# neodk_v1.net
KiCad netlist of a schematic drawn in EAGLE
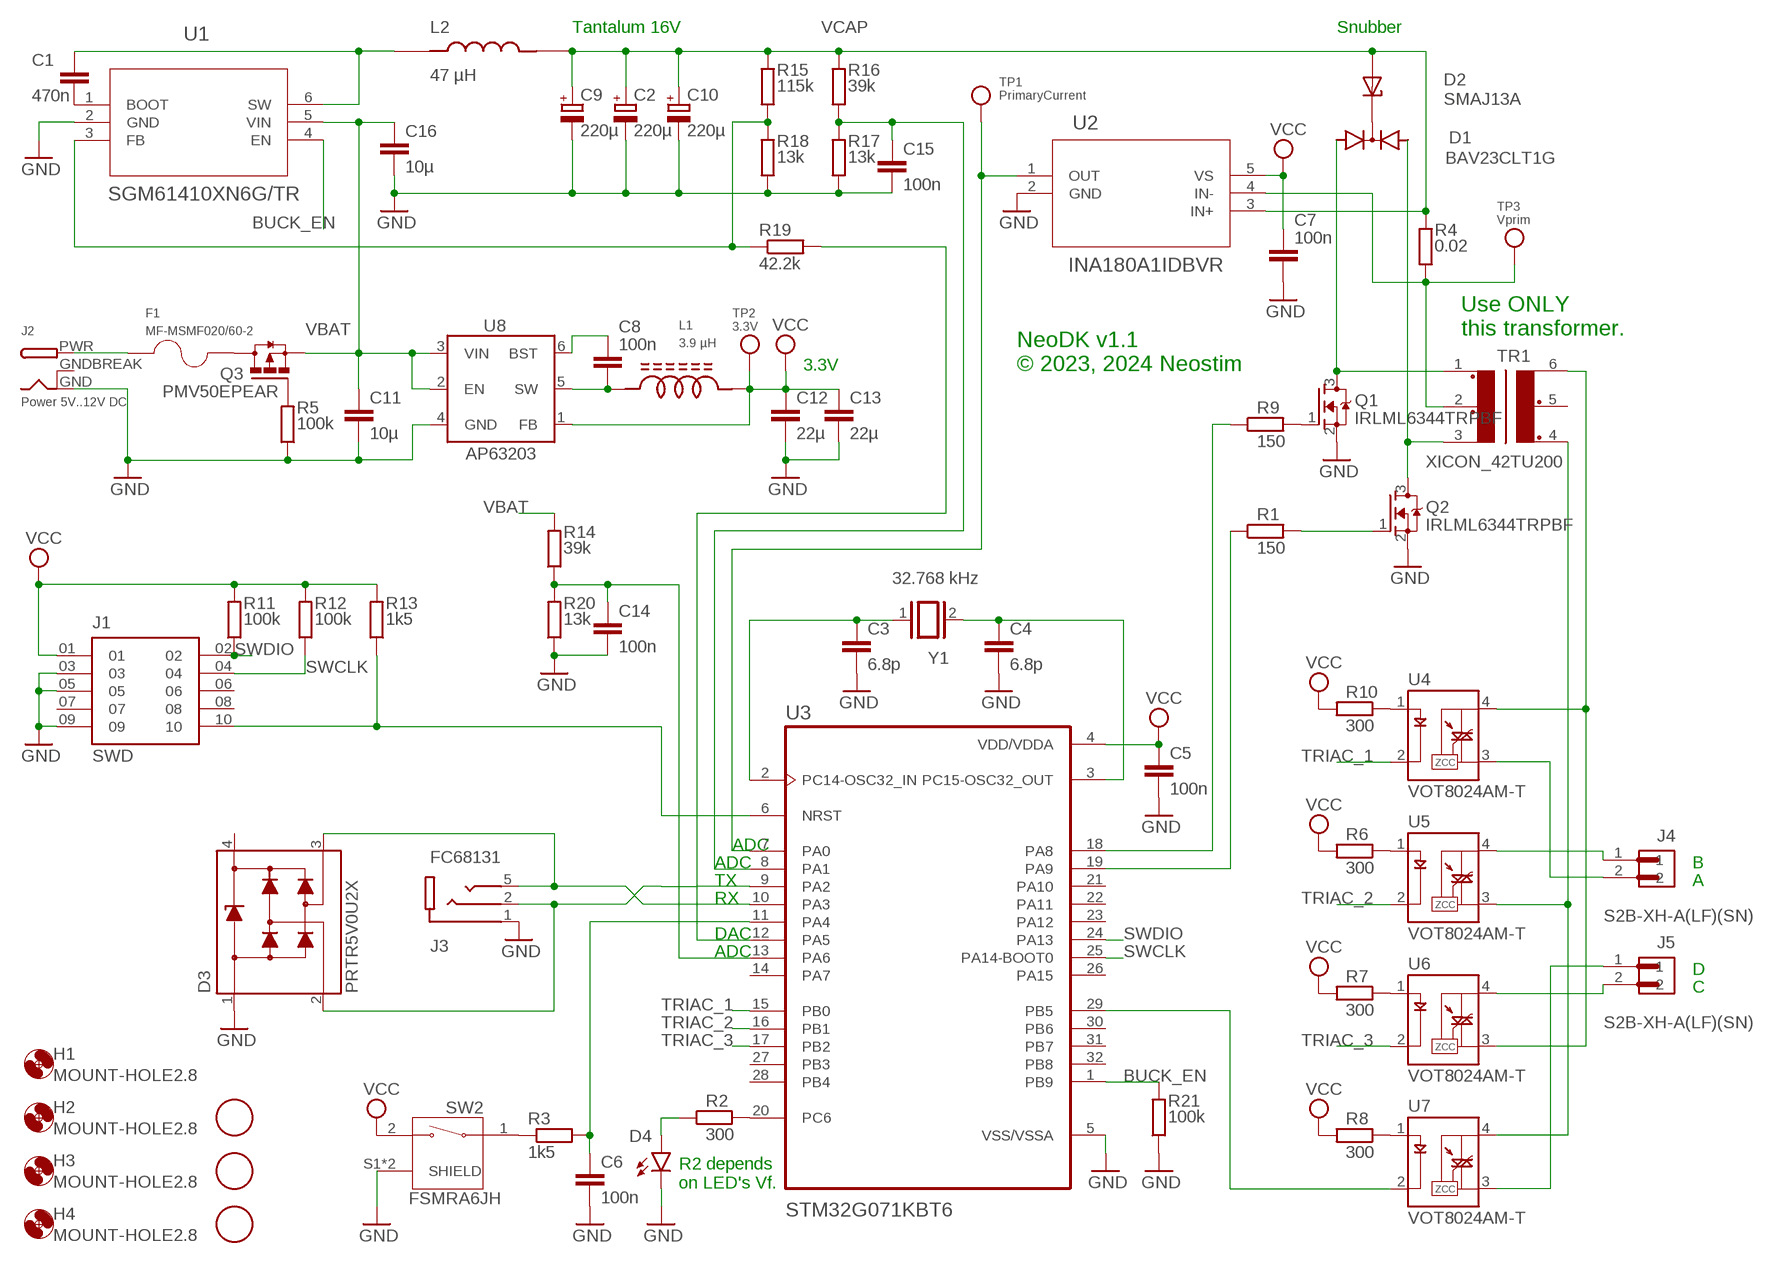
[diagram p0: schematic, sheet 1]

(export (version "E")
  (design (tool "Eeschema 10.0.6"))
  (components
    (comp (ref "C1")
      (value "470n")
      (footprint "eagle-import:C0603")
      (libsource (lib "eagle-import") (part "C-EUC0603"))
    )
    (comp (ref "C2")
      (value "220µ")
      (footprint "eagle-import:SMC_D")
      (fields (field (name "MP") "TPSE227M016R0150"))
      (libsource (lib "eagle-import") (part "CPOL-EUSMCD"))
    )
    (comp (ref "C3")
      (value "6.8p")
      (footprint "eagle-import:C0603")
      (libsource (lib "eagle-import") (part "C-EUC0603"))
    )
    (comp (ref "C4")
      (value "6.8p")
      (footprint "eagle-import:C0603")
      (libsource (lib "eagle-import") (part "C-EUC0603"))
    )
    (comp (ref "C5")
      (value "100n")
      (footprint "eagle-import:C0603")
      (libsource (lib "eagle-import") (part "C-EUC0603"))
    )
    (comp (ref "C6")
      (value "100n")
      (footprint "eagle-import:C0603")
      (libsource (lib "eagle-import") (part "C-EUC0603"))
    )
    (comp (ref "C7")
      (value "100n")
      (footprint "eagle-import:C0603")
      (libsource (lib "eagle-import") (part "C-EUC0603"))
    )
    (comp (ref "C8")
      (value "100n")
      (footprint "eagle-import:C0603")
      (libsource (lib "eagle-import") (part "C-EUC0603"))
    )
    (comp (ref "C9")
      (value "220µ")
      (footprint "eagle-import:SMC_D")
      (fields (field (name "MP") "TPSE227M016R0150"))
      (libsource (lib "eagle-import") (part "CPOL-EUSMCD"))
    )
    (comp (ref "C10")
      (value "220µ")
      (footprint "eagle-import:SMC_D")
      (fields (field (name "MP") "TPSE227M016R0150"))
      (libsource (lib "eagle-import") (part "CPOL-EUSMCD"))
    )
    (comp (ref "C11")
      (value "10µ")
      (footprint "eagle-import:C0603")
      (libsource (lib "eagle-import") (part "C-EUC0603"))
    )
    (comp (ref "C12")
      (value "22µ")
      (footprint "eagle-import:C0603")
      (libsource (lib "eagle-import") (part "C-EUC0603"))
    )
    (comp (ref "C13")
      (value "22µ")
      (footprint "eagle-import:C0603")
      (libsource (lib "eagle-import") (part "C-EUC0603"))
    )
    (comp (ref "C14")
      (value "100n")
      (footprint "eagle-import:C0603")
      (libsource (lib "eagle-import") (part "C-EUC0603"))
    )
    (comp (ref "C15")
      (value "100n")
      (footprint "eagle-import:C0603")
      (libsource (lib "eagle-import") (part "C-EUC0603"))
    )
    (comp (ref "C16")
      (value "10µ")
      (footprint "eagle-import:C0603")
      (libsource (lib "eagle-import") (part "C-EUC0603"))
    )
    (comp (ref "D1")
      (value "BAV23CLT1G")
      (footprint "eagle-import:SOT23")
      (libsource (lib "eagle-import") (part "DIODE-2AC|CASOT23"))
    )
    (comp (ref "D2")
      (value "SMAJ13A")
      (footprint "eagle-import:DIOM4325X250N")
      (fields (field (name "MF") "STMicroelectronics") (field (name "MP") "SMAJ13A-TR"))
      (libsource (lib "eagle-import") (part "SMAJ13A"))
    )
    (comp (ref "D3")
      (value "PRTR5V0U2X")
      (footprint "eagle-import:SOT190P230X110-4N")
      (fields (field (name "MF") "Nexperia USA"))
      (libsource (lib "eagle-import") (part "PRTR5V0U2X"))
    )
    (comp (ref "D4")
      (value "LEDCHIP-LED0805")
      (footprint "eagle-import:CHIP-LED0805")
      (libsource (lib "eagle-import") (part "LEDCHIP-LED0805"))
    )
    (comp (ref "F1")
      (value "MF-MSMF020/60-2")
      (footprint "eagle-import:FUSER_MF-MSMF020_60-2")
      (fields (field (name "MF") "Bourns"))
      (libsource (lib "eagle-import") (part "MF-MSMF020/60-2"))
    )
    (comp (ref "FID1")
      (value "FIDUCIAL")
      (footprint "eagle-import:FIDUCIAL_1MM")
      (libsource (lib "eagle-import") (part "FIDUCIAL"))
    )
    (comp (ref "FID2")
      (value "FIDUCIAL")
      (footprint "eagle-import:FIDUCIAL_1MM")
      (libsource (lib "eagle-import") (part "FIDUCIAL"))
    )
    (comp (ref "FID3")
      (value "FIDUCIAL")
      (footprint "eagle-import:FIDUCIAL_1MM")
      (libsource (lib "eagle-import") (part "FIDUCIAL"))
    )
    (comp (ref "H1")
      (value "MOUNT-HOLE2.8")
      (footprint "eagle-import:2,8")
      (libsource (lib "eagle-import") (part "MOUNT-HOLE2.8"))
    )
    (comp (ref "H2")
      (value "MOUNT-HOLE2.8")
      (footprint "eagle-import:2,8")
      (libsource (lib "eagle-import") (part "MOUNT-HOLE2.8"))
    )
    (comp (ref "H3")
      (value "MOUNT-HOLE2.8")
      (footprint "eagle-import:2,8")
      (libsource (lib "eagle-import") (part "MOUNT-HOLE2.8"))
    )
    (comp (ref "H4")
      (value "MOUNT-HOLE2.8")
      (footprint "eagle-import:2,8")
      (libsource (lib "eagle-import") (part "MOUNT-HOLE2.8"))
    )
    (comp (ref "J1")
      (value "SWD")
      (footprint "eagle-import:SAMTEC_FTSH-105-XX-X-DV")
      (fields (field (name "MF") "Samtec") (field (name "MP") "FTSH-105-01-L-DV"))
      (libsource (lib "eagle-import") (part "FTSH-105-XX-X-DV"))
    )
    (comp (ref "J2")
      (value "Power 5V..12V DC")
      (footprint "eagle-import:DCJACK_2MM_PTH")
      (libsource (lib "eagle-import") (part "DCBARRELPTH"))
    )
    (comp (ref "J3")
      (value "FC68131")
      (footprint "eagle-import:CLIFF_FC68131")
      (fields (field (name "MF") "Cliff"))
      (libsource (lib "eagle-import") (part "FC68131"))
    )
    (comp (ref "J4")
      (value "S2B-XH-A(LF)(SN)")
      (footprint "eagle-import:JST_S2B-XH-A(LF)(SN)")
      (fields (field (name "MF") "JST Sales"))
      (libsource (lib "eagle-import") (part "S2B-XH-A(LF)(SN)"))
    )
    (comp (ref "J5")
      (value "S2B-XH-A(LF)(SN)")
      (footprint "eagle-import:JST_S2B-XH-A(LF)(SN)")
      (fields (field (name "MF") "JST Sales"))
      (libsource (lib "eagle-import") (part "S2B-XH-A(LF)(SN)"))
    )
    (comp (ref "L1")
      (value "3.9 µH")
      (footprint "eagle-import:IND_SRR4818A-3R9Y")
      (fields (field (name "MF") "Bourns Inc.") (field (name "MP") "SRR4818A-3R9Y"))
      (libsource (lib "eagle-import") (part "SRR4818A-3R9Y"))
    )
    (comp (ref "L2")
      (value "47 µH")
      (footprint "eagle-import:IND_CLF7045NIT-470M-D")
      (fields (field (name "MF") "TDK") (field (name "MP") "CLF7045NIT-470M-D"))
      (libsource (lib "eagle-import") (part "CLF7045NIT-470M-D"))
    )
    (comp (ref "Q1")
      (value "IRLML6344TRPBF")
      (footprint "eagle-import:SOT23")
      (libsource (lib "eagle-import") (part "MOSFET-NREFLOW"))
    )
    (comp (ref "Q2")
      (value "IRLML6344TRPBF")
      (footprint "eagle-import:SOT23")
      (libsource (lib "eagle-import") (part "MOSFET-NREFLOW"))
    )
    (comp (ref "Q3")
      (value "PMV50EPEAR")
      (footprint "eagle-import:SOT23")
      (libsource (lib "eagle-import") (part "PMV50EPEAR"))
    )
    (comp (ref "R1")
      (value "150")
      (footprint "eagle-import:R0603")
      (libsource (lib "eagle-import") (part "R-EU_R0603"))
    )
    (comp (ref "R2")
      (value "300")
      (footprint "eagle-import:R0603")
      (libsource (lib "eagle-import") (part "R-EU_R0603"))
    )
    (comp (ref "R3")
      (value "1k5")
      (footprint "eagle-import:R0603")
      (libsource (lib "eagle-import") (part "R-EU_R0603"))
    )
    (comp (ref "R4")
      (value "0.02")
      (footprint "eagle-import:R1206")
      (libsource (lib "eagle-import") (part "R-EU_R1206"))
    )
    (comp (ref "R5")
      (value "100k")
      (footprint "eagle-import:R0603")
      (libsource (lib "eagle-import") (part "R-EU_R0603"))
    )
    (comp (ref "R6")
      (value "300")
      (footprint "eagle-import:R0603")
      (libsource (lib "eagle-import") (part "R-EU_R0603"))
    )
    (comp (ref "R7")
      (value "300")
      (footprint "eagle-import:R0603")
      (libsource (lib "eagle-import") (part "R-EU_R0603"))
    )
    (comp (ref "R8")
      (value "300")
      (footprint "eagle-import:R0603")
      (libsource (lib "eagle-import") (part "R-EU_R0603"))
    )
    (comp (ref "R9")
      (value "150")
      (footprint "eagle-import:R0603")
      (libsource (lib "eagle-import") (part "R-EU_R0603"))
    )
    (comp (ref "R10")
      (value "300")
      (footprint "eagle-import:R0603")
      (libsource (lib "eagle-import") (part "R-EU_R0603"))
    )
    (comp (ref "R11")
      (value "100k")
      (footprint "eagle-import:R0603")
      (libsource (lib "eagle-import") (part "R-EU_R0603"))
    )
    (comp (ref "R12")
      (value "100k")
      (footprint "eagle-import:R0603")
      (libsource (lib "eagle-import") (part "R-EU_R0603"))
    )
    (comp (ref "R13")
      (value "1k5")
      (footprint "eagle-import:R0603")
      (libsource (lib "eagle-import") (part "R-EU_R0603"))
    )
    (comp (ref "R14")
      (value "39k")
      (footprint "eagle-import:R0603")
      (libsource (lib "eagle-import") (part "R-EU_R0603"))
    )
    (comp (ref "R15")
      (value "115k")
      (footprint "eagle-import:R0603")
      (libsource (lib "eagle-import") (part "R-EU_R0603"))
    )
    (comp (ref "R16")
      (value "39k")
      (footprint "eagle-import:R0603")
      (libsource (lib "eagle-import") (part "R-EU_R0603"))
    )
    (comp (ref "R17")
      (value "13k")
      (footprint "eagle-import:R0603")
      (libsource (lib "eagle-import") (part "R-EU_R0603"))
    )
    (comp (ref "R18")
      (value "13k")
      (footprint "eagle-import:R0603")
      (libsource (lib "eagle-import") (part "R-EU_R0603"))
    )
    (comp (ref "R19")
      (value "42.2k")
      (footprint "eagle-import:R0603")
      (libsource (lib "eagle-import") (part "R-EU_R0603"))
    )
    (comp (ref "R20")
      (value "13k")
      (footprint "eagle-import:R0603")
      (libsource (lib "eagle-import") (part "R-EU_R0603"))
    )
    (comp (ref "R21")
      (value "100k")
      (footprint "eagle-import:R0603")
      (libsource (lib "eagle-import") (part "R-EU_R0603"))
    )
    (comp (ref "SW2")
      (value "FSMRA6JH")
      (footprint "eagle-import:TE_FSMRA6JH")
      (fields (field (name "MF") "TE Connectivity"))
      (libsource (lib "eagle-import") (part "FSMRA6JH"))
    )
    (comp (ref "TP1")
      (value "PrimaryCurrent")
      (footprint "eagle-import:TESTPOINT_ROUND_1MM")
      (libsource (lib "eagle-import") (part "TESTPOINTROUND1MM"))
    )
    (comp (ref "TP2")
      (value "3.3V")
      (footprint "eagle-import:TESTPOINT_ROUND_1MM")
      (libsource (lib "eagle-import") (part "TESTPOINTROUND1MM"))
    )
    (comp (ref "TP3")
      (value "Vprim")
      (footprint "eagle-import:TESTPOINT_ROUND_1MM")
      (libsource (lib "eagle-import") (part "TESTPOINTROUND1MM"))
    )
    (comp (ref "TR1")
      (value "XICON_42TU200")
      (footprint "eagle-import:42TUXXX")
      (libsource (lib "eagle-import") (part "XICON_42TU200"))
    )
    (comp (ref "U1")
      (value "SGM61410XN6G/TR")
      (footprint "eagle-import:SOT-23-6_SNC")
      (libsource (lib "eagle-import") (part "SGM61410XN6G/TR"))
    )
    (comp (ref "U2")
      (value "INA180A1IDBVR")
      (footprint "eagle-import:DBV5")
      (libsource (lib "eagle-import") (part "INA180A1IDBVR"))
    )
    (comp (ref "U3")
      (value "STM32G071KBT6")
      (footprint "eagle-import:QFP80P900X900X160-32N")
      (fields (field (name "MF") "STMicroelectronics") (field (name "MP") "STM32G070KBT6"))
      (libsource (lib "eagle-import") (part "STM32G071KBT6"))
    )
    (comp (ref "U4")
      (value "VOT8024AM-T")
      (footprint "eagle-import:SOP254P675X240-4N")
      (fields (field (name "MF") "Vishay Semiconductor Opto Division"))
      (libsource (lib "eagle-import") (part "VOT8024AM-T"))
    )
    (comp (ref "U5")
      (value "VOT8024AM-T")
      (footprint "eagle-import:SOP254P675X240-4N")
      (fields (field (name "MF") "Vishay Semiconductor Opto Division"))
      (libsource (lib "eagle-import") (part "VOT8024AM-T"))
    )
    (comp (ref "U6")
      (value "VOT8024AM-T")
      (footprint "eagle-import:SOP254P675X240-4N")
      (fields (field (name "MF") "Vishay Semiconductor Opto Division"))
      (libsource (lib "eagle-import") (part "VOT8024AM-T"))
    )
    (comp (ref "U7")
      (value "VOT8024AM-T")
      (footprint "eagle-import:SOP254P675X240-4N")
      (fields (field (name "MF") "Vishay Semiconductor Opto Division"))
      (libsource (lib "eagle-import") (part "VOT8024AM-T"))
    )
    (comp (ref "U8")
      (value "AP63203")
      (footprint "eagle-import:SOT23-6")
      (fields (field (name "MF") "Diodes Zetex"))
      (libsource (lib "eagle-import") (part "AP63203"))
    )
    (comp (ref "Y1")
      (value "32.768 kHz")
      (footprint "eagle-import:XTAL_NX3215SA-32.768K-STD-MUA-8")
      (fields (field (name "MF") "NDK America,") (field (name "MP") "NX3215SA-32.768K-STD-MUA-8"))
      (libsource (lib "eagle-import") (part "NX3215SA-32.768K-STD-MUA-8"))
    )
  )
  (nets
    (net (code "1") (name "/BUCK_EN") (class "Default")
      (node (ref "R21") (pin "2") (pinfunction "2_2") (pintype "passive"))
      (node (ref "U1") (pin "4") (pinfunction "EN_4") (pintype "passive"))
      (node (ref "U3") (pin "1") (pinfunction "PB9_1") (pintype "bidirectional"))
    )
    (net (code "2") (name "/GNDBREAK") (class "Default")
      (node (ref "J2") (pin "GNDBREAK") (pinfunction "GNDBREAK_GNDBREAK") (pintype "power_in"))
    )
    (net (code "3") (name "/SWCLK") (class "Default")
      (node (ref "J1") (pin "04") (pinfunction "04_04") (pintype "passive"))
      (node (ref "R12") (pin "1") (pinfunction "1_1") (pintype "passive"))
      (node (ref "U3") (pin "25") (pinfunction "PA14-BOOT0_25") (pintype "bidirectional"))
    )
    (net (code "4") (name "/SWDIO") (class "Default")
      (node (ref "J1") (pin "02") (pinfunction "02_02") (pintype "passive"))
      (node (ref "R11") (pin "1") (pinfunction "1_1") (pintype "passive"))
      (node (ref "U3") (pin "24") (pinfunction "PA13_24") (pintype "bidirectional"))
    )
    (net (code "5") (name "/TRIAC_1") (class "Default")
      (node (ref "U3") (pin "15") (pinfunction "PB0_15") (pintype "bidirectional"))
      (node (ref "U4") (pin "2") (pinfunction "C_2") (pintype "passive"))
    )
    (net (code "6") (name "/TRIAC_2") (class "Default")
      (node (ref "U3") (pin "16") (pinfunction "PB1_16") (pintype "bidirectional"))
      (node (ref "U5") (pin "2") (pinfunction "C_2") (pintype "passive"))
    )
    (net (code "7") (name "/TRIAC_3") (class "Default")
      (node (ref "U3") (pin "17") (pinfunction "PB2_17") (pintype "bidirectional"))
      (node (ref "U6") (pin "2") (pinfunction "C_2") (pintype "passive"))
    )
    (net (code "8") (name "/VBAT") (class "Default")
      (node (ref "C11") (pin "1") (pinfunction "1_1") (pintype "passive"))
      (node (ref "C16") (pin "1") (pinfunction "1_1") (pintype "passive"))
      (node (ref "Q3") (pin "3") (pinfunction "S_3") (pintype "passive"))
      (node (ref "R14") (pin "2") (pinfunction "2_2") (pintype "passive"))
      (node (ref "U1") (pin "5") (pinfunction "VIN_5") (pintype "power_in"))
      (node (ref "U8") (pin "2") (pinfunction "EN_2") (pintype "bidirectional"))
      (node (ref "U8") (pin "3") (pinfunction "VIN_3") (pintype "bidirectional"))
    )
    (net (code "9") (name "/VCAP") (class "Default")
      (node (ref "C10") (pin "+") (pinfunction "+_+") (pintype "passive"))
      (node (ref "C2") (pin "+") (pinfunction "+_+") (pintype "passive"))
      (node (ref "C9") (pin "+") (pinfunction "+_+") (pintype "passive"))
      (node (ref "D2") (pin "A") (pinfunction "A_A") (pintype "passive"))
      (node (ref "L2") (pin "2") (pinfunction "2_2") (pintype "passive"))
      (node (ref "R15") (pin "2") (pinfunction "2_2") (pintype "passive"))
      (node (ref "R16") (pin "2") (pinfunction "2_2") (pintype "passive"))
      (node (ref "R4") (pin "2") (pinfunction "2_2") (pintype "passive"))
      (node (ref "U2") (pin "3") (pinfunction "IN+_3") (pintype "input"))
    )
    (net (code "10") (name "GND") (class "Default")
      (node (ref "C10") (pin "-") (pinfunction "-_-") (pintype "passive"))
      (node (ref "C11") (pin "2") (pinfunction "2_2") (pintype "passive"))
      (node (ref "C12") (pin "2") (pinfunction "2_2") (pintype "passive"))
      (node (ref "C13") (pin "2") (pinfunction "2_2") (pintype "passive"))
      (node (ref "C14") (pin "2") (pinfunction "2_2") (pintype "passive"))
      (node (ref "C15") (pin "2") (pinfunction "2_2") (pintype "passive"))
      (node (ref "C16") (pin "2") (pinfunction "2_2") (pintype "passive"))
      (node (ref "C2") (pin "-") (pinfunction "-_-") (pintype "passive"))
      (node (ref "C3") (pin "2") (pinfunction "2_2") (pintype "passive"))
      (node (ref "C4") (pin "2") (pinfunction "2_2") (pintype "passive"))
      (node (ref "C5") (pin "2") (pinfunction "2_2") (pintype "passive"))
      (node (ref "C6") (pin "2") (pinfunction "2_2") (pintype "passive"))
      (node (ref "C7") (pin "2") (pinfunction "2_2") (pintype "passive"))
      (node (ref "C9") (pin "-") (pinfunction "-_-") (pintype "passive"))
      (node (ref "D3") (pin "1") (pinfunction "GND_1") (pintype "passive"))
      (node (ref "D4") (pin "C") (pinfunction "C_C") (pintype "passive"))
      (node (ref "J1") (pin "03") (pinfunction "03_03") (pintype "passive"))
      (node (ref "J1") (pin "05") (pinfunction "05_05") (pintype "passive"))
      (node (ref "J1") (pin "09") (pinfunction "09_09") (pintype "passive"))
      (node (ref "J2") (pin "GND") (pinfunction "GND_GND") (pintype "power_in"))
      (node (ref "J3") (pin "1") (pinfunction "SLEEVE_1") (pintype "passive"))
      (node (ref "Q1") (pin "2") (pinfunction "S_2") (pintype "bidirectional"))
      (node (ref "Q2") (pin "2") (pinfunction "S_2") (pintype "bidirectional"))
      (node (ref "R17") (pin "1") (pinfunction "1_1") (pintype "passive"))
      (node (ref "R18") (pin "1") (pinfunction "1_1") (pintype "passive"))
      (node (ref "R20") (pin "1") (pinfunction "1_1") (pintype "passive"))
      (node (ref "R21") (pin "1") (pinfunction "1_1") (pintype "passive"))
      (node (ref "R5") (pin "1") (pinfunction "1_1") (pintype "passive"))
      (node (ref "SW2") (pin "S1") (pinfunction "SHIELD_S1") (pintype "passive"))
      (node (ref "SW2") (pin "S2") (pinfunction "SHIELD_S2") (pintype "passive"))
      (node (ref "U1") (pin "2") (pinfunction "GND_2") (pintype "passive"))
      (node (ref "U2") (pin "2") (pinfunction "GND_2") (pintype "power_in"))
      (node (ref "U3") (pin "5") (pinfunction "VSS/VSSA_5") (pintype "power_in"))
      (node (ref "U8") (pin "4") (pinfunction "GND_4") (pintype "bidirectional"))
    )
    (net (code "11") (name "Net-(D1-A1)") (class "Default")
      (node (ref "D1") (pin "1") (pinfunction "A1_1") (pintype "passive"))
      (node (ref "Q1") (pin "3") (pinfunction "D_3") (pintype "bidirectional"))
      (node (ref "TR1") (pin "1") (pinfunction "1_1") (pintype "passive"))
    )
    (net (code "12") (name "Net-(D1-A2)") (class "Default")
      (node (ref "D1") (pin "2") (pinfunction "A2_2") (pintype "passive"))
      (node (ref "Q2") (pin "3") (pinfunction "D_3") (pintype "bidirectional"))
      (node (ref "TR1") (pin "3") (pinfunction "3_3") (pintype "passive"))
    )
    (net (code "13") (name "Net-(D1-C)") (class "Default")
      (node (ref "D1") (pin "3") (pinfunction "C_3") (pintype "passive"))
      (node (ref "D2") (pin "C") (pinfunction "C_C") (pintype "passive"))
    )
    (net (code "14") (name "Net-(D3-I{slash}O_1)") (class "Default")
      (node (ref "D3") (pin "2") (pinfunction "I/O_1_2") (pintype "passive"))
      (node (ref "J3") (pin "2") (pinfunction "RING_2") (pintype "passive"))
      (node (ref "U3") (pin "9") (pinfunction "PA2_9") (pintype "bidirectional"))
    )
    (net (code "15") (name "Net-(D3-I{slash}O_2)") (class "Default")
      (node (ref "D3") (pin "3") (pinfunction "I/O_2_3") (pintype "passive"))
      (node (ref "J3") (pin "5") (pinfunction "TIP_5") (pintype "passive"))
      (node (ref "U3") (pin "10") (pinfunction "PA3_10") (pintype "bidirectional"))
    )
    (net (code "16") (name "Net-(D4-PadA)") (class "Default")
      (node (ref "D4") (pin "A") (pinfunction "A_A") (pintype "passive"))
      (node (ref "R2") (pin "1") (pinfunction "1_1") (pintype "passive"))
    )
    (net (code "17") (name "Net-(F1-Pad1)") (class "Default")
      (node (ref "F1") (pin "1") (pinfunction "1_1") (pintype "passive"))
      (node (ref "J2") (pin "PWR") (pinfunction "PWR_PWR") (pintype "power_in"))
    )
    (net (code "18") (name "Net-(Q1-G)") (class "Default")
      (node (ref "Q1") (pin "1") (pinfunction "G_1") (pintype "bidirectional"))
      (node (ref "R9") (pin "2") (pinfunction "2_2") (pintype "passive"))
    )
    (net (code "19") (name "Net-(Q2-G)") (class "Default")
      (node (ref "Q2") (pin "1") (pinfunction "G_1") (pintype "bidirectional"))
      (node (ref "R1") (pin "2") (pinfunction "2_2") (pintype "passive"))
    )
    (net (code "20") (name "Net-(Q3-D)") (class "Default")
      (node (ref "F1") (pin "2") (pinfunction "2_2") (pintype "passive"))
      (node (ref "Q3") (pin "2") (pinfunction "D_2") (pintype "passive"))
    )
    (net (code "21") (name "Net-(Q3-G)") (class "Default")
      (node (ref "Q3") (pin "1") (pinfunction "G_1") (pintype "passive"))
      (node (ref "R5") (pin "2") (pinfunction "2_2") (pintype "passive"))
    )
    (net (code "22") (name "Net-(R3-Pad1)") (class "Default")
      (node (ref "R3") (pin "1") (pinfunction "1_1") (pintype "passive"))
      (node (ref "SW2") (pin "1") (pinfunction "1_1") (pintype "passive"))
    )
    (net (code "23") (name "Net-(U1-BOOT)") (class "Default")
      (node (ref "C1") (pin "2") (pinfunction "2_2") (pintype "passive"))
      (node (ref "U1") (pin "1") (pinfunction "BOOT_1") (pintype "passive"))
    )
    (net (code "24") (name "Net-(U1-FB)") (class "Default")
      (node (ref "R15") (pin "1") (pinfunction "1_1") (pintype "passive"))
      (node (ref "R18") (pin "2") (pinfunction "2_2") (pintype "passive"))
      (node (ref "R19") (pin "1") (pinfunction "1_1") (pintype "passive"))
      (node (ref "U1") (pin "3") (pinfunction "FB_3") (pintype "passive"))
    )
    (net (code "25") (name "Net-(U1-SW)") (class "Default")
      (node (ref "C1") (pin "1") (pinfunction "1_1") (pintype "passive"))
      (node (ref "L2") (pin "1") (pinfunction "1_1") (pintype "passive"))
      (node (ref "U1") (pin "6") (pinfunction "SW_6") (pintype "output"))
    )
    (net (code "26") (name "Net-(U2-IN-)") (class "Default")
      (node (ref "R4") (pin "1") (pinfunction "1_1") (pintype "passive"))
      (node (ref "TP3") (pin "P$1") (pinfunction "P$1_P$1") (pintype "bidirectional"))
      (node (ref "TR1") (pin "2") (pinfunction "2_2") (pintype "passive"))
      (node (ref "U2") (pin "4") (pinfunction "IN-_4") (pintype "input"))
    )
    (net (code "27") (name "Net-(U2-OUT)") (class "Default")
      (node (ref "TP1") (pin "P$1") (pinfunction "P$1_P$1") (pintype "bidirectional"))
      (node (ref "U2") (pin "1") (pinfunction "OUT_1") (pintype "output"))
      (node (ref "U3") (pin "7") (pinfunction "PA0_7") (pintype "bidirectional"))
    )
    (net (code "28") (name "Net-(U3-NRST)") (class "Default")
      (node (ref "J1") (pin "10") (pinfunction "10_10") (pintype "passive"))
      (node (ref "R13") (pin "1") (pinfunction "1_1") (pintype "passive"))
      (node (ref "U3") (pin "6") (pinfunction "NRST_6") (pintype "bidirectional"))
    )
    (net (code "29") (name "Net-(U3-PA1)") (class "Default")
      (node (ref "C15") (pin "1") (pinfunction "1_1") (pintype "passive"))
      (node (ref "R16") (pin "1") (pinfunction "1_1") (pintype "passive"))
      (node (ref "R17") (pin "2") (pinfunction "2_2") (pintype "passive"))
      (node (ref "U3") (pin "8") (pinfunction "PA1_8") (pintype "bidirectional"))
    )
    (net (code "30") (name "Net-(U3-PA4)") (class "Default")
      (node (ref "C6") (pin "1") (pinfunction "1_1") (pintype "passive"))
      (node (ref "R3") (pin "2") (pinfunction "2_2") (pintype "passive"))
      (node (ref "U3") (pin "11") (pinfunction "PA4_11") (pintype "bidirectional"))
    )
    (net (code "31") (name "Net-(U3-PA5)") (class "Default")
      (node (ref "R19") (pin "2") (pinfunction "2_2") (pintype "passive"))
      (node (ref "U3") (pin "12") (pinfunction "PA5_12") (pintype "bidirectional"))
    )
    (net (code "32") (name "Net-(U3-PA6)") (class "Default")
      (node (ref "C14") (pin "1") (pinfunction "1_1") (pintype "passive"))
      (node (ref "R14") (pin "1") (pinfunction "1_1") (pintype "passive"))
      (node (ref "R20") (pin "2") (pinfunction "2_2") (pintype "passive"))
      (node (ref "U3") (pin "13") (pinfunction "PA6_13") (pintype "bidirectional"))
    )
    (net (code "33") (name "Net-(U3-PA8)") (class "Default")
      (node (ref "R9") (pin "1") (pinfunction "1_1") (pintype "passive"))
      (node (ref "U3") (pin "18") (pinfunction "PA8_18") (pintype "bidirectional"))
    )
    (net (code "34") (name "Net-(U3-PA9)") (class "Default")
      (node (ref "R1") (pin "1") (pinfunction "1_1") (pintype "passive"))
      (node (ref "U3") (pin "19") (pinfunction "PA9_19") (pintype "bidirectional"))
    )
    (net (code "35") (name "Net-(U3-PB5)") (class "Default")
      (node (ref "U3") (pin "29") (pinfunction "PB5_29") (pintype "bidirectional"))
      (node (ref "U7") (pin "2") (pinfunction "C_2") (pintype "passive"))
    )
    (net (code "36") (name "Net-(U3-PC6)") (class "Default")
      (node (ref "R2") (pin "2") (pinfunction "2_2") (pintype "passive"))
      (node (ref "U3") (pin "20") (pinfunction "PC6_20") (pintype "bidirectional"))
    )
    (net (code "37") (name "Net-(U3-PC14-OSC32_IN)") (class "Default")
      (node (ref "C3") (pin "1") (pinfunction "1_1") (pintype "passive"))
      (node (ref "U3") (pin "2") (pinfunction "PC14-OSC32_IN_2") (pintype "input"))
      (node (ref "Y1") (pin "1") (pinfunction "1_1") (pintype "passive"))
    )
    (net (code "38") (name "Net-(U3-PC15-OSC32_OUT)") (class "Default")
      (node (ref "C4") (pin "1") (pinfunction "1_1") (pintype "passive"))
      (node (ref "U3") (pin "3") (pinfunction "PC15-OSC32_OUT_3") (pintype "output"))
      (node (ref "Y1") (pin "2") (pinfunction "2_2") (pintype "passive"))
    )
    (net (code "39") (name "Net-(U4-A)") (class "Default")
      (node (ref "R10") (pin "1") (pinfunction "1_1") (pintype "passive"))
      (node (ref "U4") (pin "1") (pinfunction "A_1") (pintype "passive"))
    )
    (net (code "40") (name "Net-(U4-MT1)") (class "Default")
      (node (ref "J4") (pin "2") (pinfunction "2_2") (pintype "passive"))
      (node (ref "U4") (pin "3") (pinfunction "MT1_3") (pintype "passive"))
    )
    (net (code "41") (name "Net-(U4-MT2)") (class "Default")
      (node (ref "TR1") (pin "6") (pinfunction "6_6") (pintype "passive"))
      (node (ref "U4") (pin "4") (pinfunction "MT2_4") (pintype "passive"))
      (node (ref "U6") (pin "3") (pinfunction "MT1_3") (pintype "passive"))
    )
    (net (code "42") (name "Net-(U5-A)") (class "Default")
      (node (ref "R6") (pin "1") (pinfunction "1_1") (pintype "passive"))
      (node (ref "U5") (pin "1") (pinfunction "A_1") (pintype "passive"))
    )
    (net (code "43") (name "Net-(U5-MT1)") (class "Default")
      (node (ref "TR1") (pin "4") (pinfunction "4_4") (pintype "passive"))
      (node (ref "U5") (pin "3") (pinfunction "MT1_3") (pintype "passive"))
      (node (ref "U7") (pin "4") (pinfunction "MT2_4") (pintype "passive"))
    )
    (net (code "44") (name "Net-(U5-MT2)") (class "Default")
      (node (ref "J4") (pin "1") (pinfunction "1_1") (pintype "passive"))
      (node (ref "U5") (pin "4") (pinfunction "MT2_4") (pintype "passive"))
    )
    (net (code "45") (name "Net-(U6-A)") (class "Default")
      (node (ref "R7") (pin "1") (pinfunction "1_1") (pintype "passive"))
      (node (ref "U6") (pin "1") (pinfunction "A_1") (pintype "passive"))
    )
    (net (code "46") (name "Net-(U6-MT2)") (class "Default")
      (node (ref "J5") (pin "2") (pinfunction "2_2") (pintype "passive"))
      (node (ref "U6") (pin "4") (pinfunction "MT2_4") (pintype "passive"))
    )
    (net (code "47") (name "Net-(U7-A)") (class "Default")
      (node (ref "R8") (pin "1") (pinfunction "1_1") (pintype "passive"))
      (node (ref "U7") (pin "1") (pinfunction "A_1") (pintype "passive"))
    )
    (net (code "48") (name "Net-(U7-MT1)") (class "Default")
      (node (ref "J5") (pin "1") (pinfunction "1_1") (pintype "passive"))
      (node (ref "U7") (pin "3") (pinfunction "MT1_3") (pintype "passive"))
    )
    (net (code "49") (name "Net-(U8-BST)") (class "Default")
      (node (ref "C8") (pin "1") (pinfunction "1_1") (pintype "passive"))
      (node (ref "U8") (pin "6") (pinfunction "BST_6") (pintype "bidirectional"))
    )
    (net (code "50") (name "Net-(U8-SW)") (class "Default")
      (node (ref "C8") (pin "2") (pinfunction "2_2") (pintype "passive"))
      (node (ref "L1") (pin "1") (pinfunction "1_1") (pintype "passive"))
      (node (ref "U8") (pin "5") (pinfunction "SW_5") (pintype "bidirectional"))
    )
    (net (code "51") (name "VCC") (class "Default")
      (node (ref "C12") (pin "1") (pinfunction "1_1") (pintype "passive"))
      (node (ref "C13") (pin "1") (pinfunction "1_1") (pintype "passive"))
      (node (ref "C5") (pin "1") (pinfunction "1_1") (pintype "passive"))
      (node (ref "C7") (pin "1") (pinfunction "1_1") (pintype "passive"))
      (node (ref "J1") (pin "01") (pinfunction "01_01") (pintype "passive"))
      (node (ref "L1") (pin "2") (pinfunction "2_2") (pintype "passive"))
      (node (ref "R10") (pin "2") (pinfunction "2_2") (pintype "passive"))
      (node (ref "R11") (pin "2") (pinfunction "2_2") (pintype "passive"))
      (node (ref "R12") (pin "2") (pinfunction "2_2") (pintype "passive"))
      (node (ref "R13") (pin "2") (pinfunction "2_2") (pintype "passive"))
      (node (ref "R6") (pin "2") (pinfunction "2_2") (pintype "passive"))
      (node (ref "R7") (pin "2") (pinfunction "2_2") (pintype "passive"))
      (node (ref "R8") (pin "2") (pinfunction "2_2") (pintype "passive"))
      (node (ref "SW2") (pin "2") (pinfunction "2_2") (pintype "passive"))
      (node (ref "TP2") (pin "P$1") (pinfunction "P$1_P$1") (pintype "bidirectional"))
      (node (ref "U2") (pin "5") (pinfunction "VS_5") (pintype "power_in"))
      (node (ref "U3") (pin "4") (pinfunction "VDD/VDDA_4") (pintype "power_in"))
      (node (ref "U8") (pin "1") (pinfunction "FB_1") (pintype "bidirectional"))
    )
    (net (code "52") (name "unconnected-(D3-VCC-Pad4)") (class "Default")
      (node (ref "D3") (pin "4") (pinfunction "VCC_4") (pintype "passive"))
    )
    (net (code "53") (name "unconnected-(J1-Pad06)") (class "Default")
      (node (ref "J1") (pin "06") (pinfunction "06_06") (pintype "passive"))
    )
    (net (code "54") (name "unconnected-(J1-Pad07)") (class "Default")
      (node (ref "J1") (pin "07") (pinfunction "07_07") (pintype "passive"))
    )
    (net (code "55") (name "unconnected-(J1-Pad08)") (class "Default")
      (node (ref "J1") (pin "08") (pinfunction "08_08") (pintype "passive"))
    )
    (net (code "56") (name "unconnected-(TR1-Pad5)") (class "Default")
      (node (ref "TR1") (pin "5") (pinfunction "5_5") (pintype "passive"))
    )
    (net (code "57") (name "unconnected-(U3-PA7-Pad14)") (class "Default")
      (node (ref "U3") (pin "14") (pinfunction "PA7_14") (pintype "bidirectional"))
    )
    (net (code "58") (name "unconnected-(U3-PA10-Pad21)") (class "Default")
      (node (ref "U3") (pin "21") (pinfunction "PA10_21") (pintype "bidirectional"))
    )
    (net (code "59") (name "unconnected-(U3-PA11-Pad22)") (class "Default")
      (node (ref "U3") (pin "22") (pinfunction "PA11_22") (pintype "bidirectional"))
    )
    (net (code "60") (name "unconnected-(U3-PA12-Pad23)") (class "Default")
      (node (ref "U3") (pin "23") (pinfunction "PA12_23") (pintype "bidirectional"))
    )
    (net (code "61") (name "unconnected-(U3-PA15-Pad26)") (class "Default")
      (node (ref "U3") (pin "26") (pinfunction "PA15_26") (pintype "bidirectional"))
    )
    (net (code "62") (name "unconnected-(U3-PB3-Pad27)") (class "Default")
      (node (ref "U3") (pin "27") (pinfunction "PB3_27") (pintype "bidirectional"))
    )
    (net (code "63") (name "unconnected-(U3-PB4-Pad28)") (class "Default")
      (node (ref "U3") (pin "28") (pinfunction "PB4_28") (pintype "bidirectional"))
    )
    (net (code "64") (name "unconnected-(U3-PB6-Pad30)") (class "Default")
      (node (ref "U3") (pin "30") (pinfunction "PB6_30") (pintype "bidirectional"))
    )
    (net (code "65") (name "unconnected-(U3-PB7-Pad31)") (class "Default")
      (node (ref "U3") (pin "31") (pinfunction "PB7_31") (pintype "bidirectional"))
    )
    (net (code "66") (name "unconnected-(U3-PB8-Pad32)") (class "Default")
      (node (ref "U3") (pin "32") (pinfunction "PB8_32") (pintype "bidirectional"))
    )
  )
)
